# FULL_WAVE_RECTIFIER_PCB.net
KiCad netlist of a schematic drawn in EasyEDA
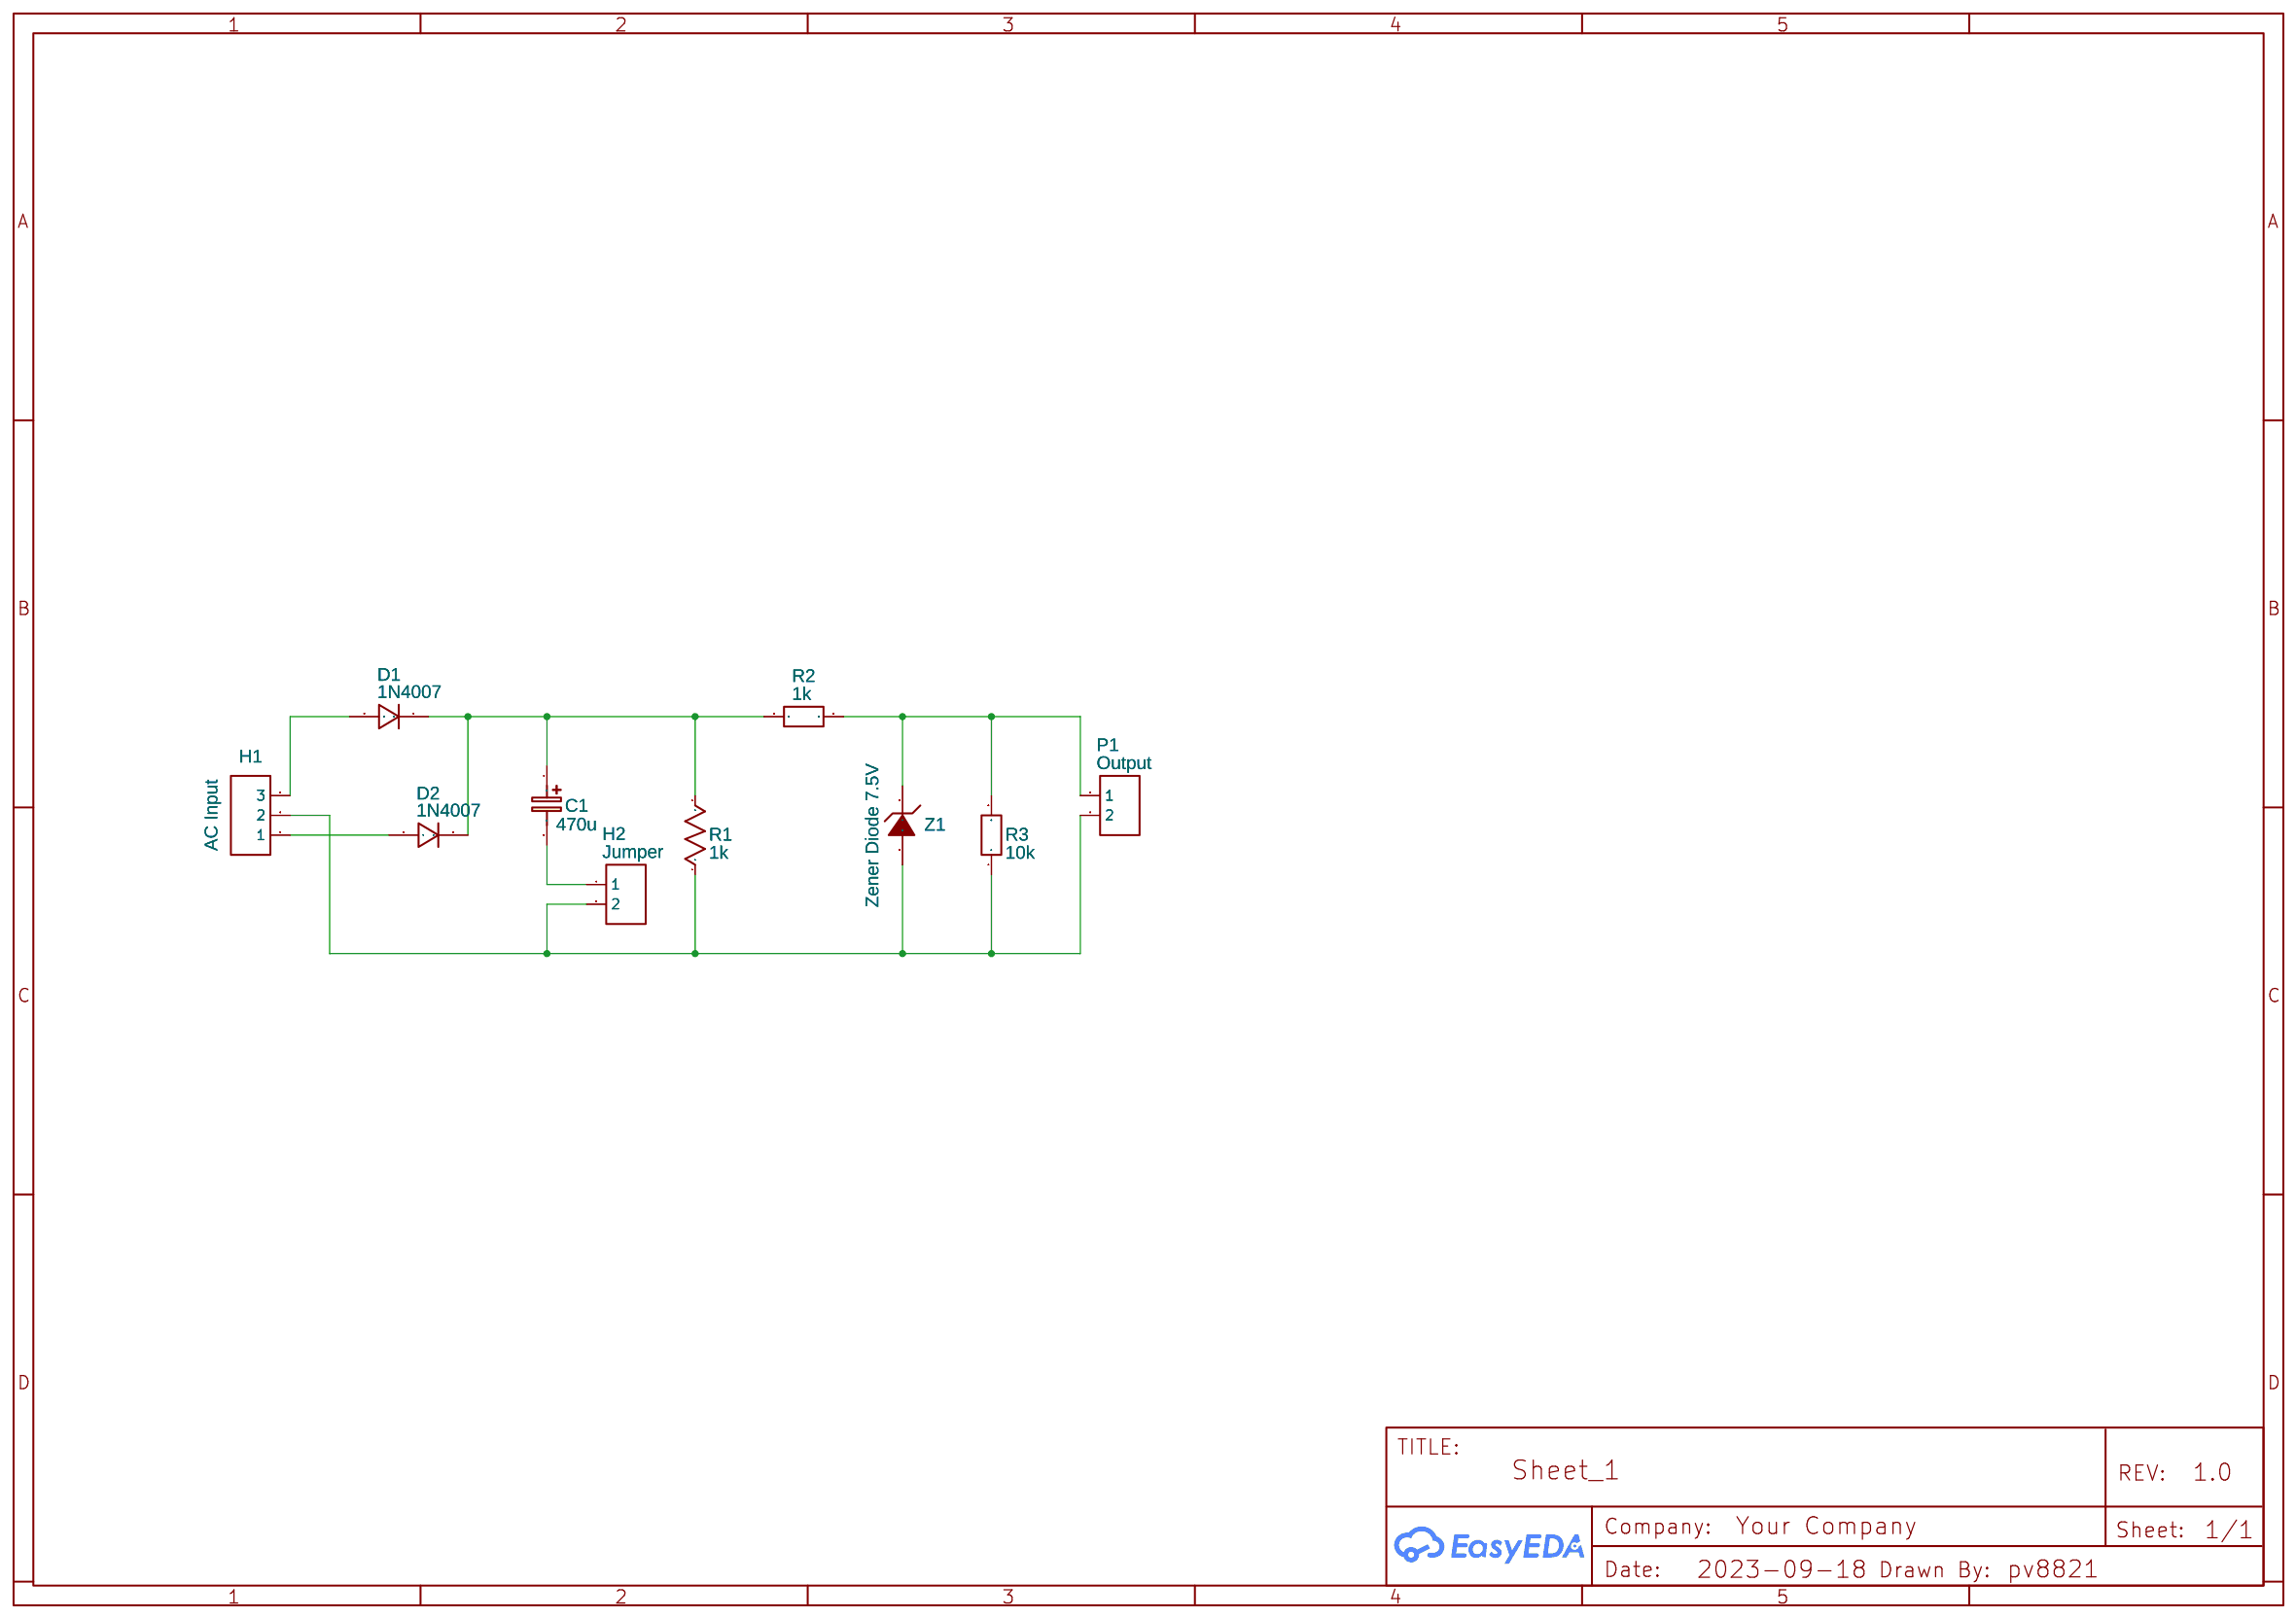
[diagram p0: schematic sheet]

(export (version "E")
  (design (tool "Eeschema 10.0.6"))
  (components
    (comp (ref "C1") (value "470u") (libsource (lib "") (part "CE_TH_D5.0×F2.0_EU")))
    (comp (ref "D1")
      (value "1N4007")
      (fields (field (name "Manufacturer") "SEMTECH"))
      (libsource (lib "") (part "1N4007"))
    )
    (comp (ref "D2")
      (value "1N4007")
      (fields (field (name "Manufacturer") "SEMTECH"))
      (libsource (lib "") (part "1N4007"))
    )
    (comp (ref "H1") (value "AC Input") (libsource (lib "") (part "HDR-F-2.54_1x3")))
    (comp (ref "H2") (value "Jumper") (libsource (lib "") (part "HDR-F-2.54_1x2")))
    (comp (ref "P1") (value "Output") (libsource (lib "") (part "CONN-TH_2P-P5.00")))
    (comp (ref "R1") (value "1k") (libsource (lib "") (part "R_AXIAL-0.5_US")))
    (comp (ref "R2") (value "1k") (libsource (lib "") (part "R_AXIAL-0.5_EU_1")))
    (comp (ref "R3") (value "10k") (libsource (lib "") (part "R_AXIAL-0.5_EU")))
    (comp (ref "Z1")
      (value "Zener Diode 7.5V")
      (fields (field (name "Manufacturer Part") "1N5349BRLG") (field (name "Manufacturer") "onsemi(安森美)"))
      (libsource (lib "") (part "1N5349BRLG"))
    )
  )
  (nets
    (net (code "1") (name "Net-(C1-Pad1)") (class "Default")
      (node (ref "C1") (pin "1") (pinfunction "1_1") (pintype "unspecified"))
      (node (ref "D1") (pin "1") (pinfunction "1_1") (pintype "unspecified"))
      (node (ref "D2") (pin "1") (pinfunction "1_1") (pintype "unspecified"))
      (node (ref "R1") (pin "2") (pinfunction "2_2") (pintype "unspecified"))
      (node (ref "R2") (pin "1") (pinfunction "1_1") (pintype "unspecified"))
    )
    (net (code "2") (name "Net-(C1-Pad2)") (class "Default")
      (node (ref "C1") (pin "2") (pinfunction "2_2") (pintype "unspecified"))
      (node (ref "H2") (pin "1") (pinfunction "1_1") (pintype "input"))
    )
    (net (code "3") (name "Net-(D1-Pad2)") (class "Default")
      (node (ref "D1") (pin "2") (pinfunction "2_2") (pintype "unspecified"))
      (node (ref "H1") (pin "3") (pinfunction "3_3") (pintype "input"))
    )
    (net (code "4") (name "Net-(D2-Pad2)") (class "Default")
      (node (ref "D2") (pin "2") (pinfunction "2_2") (pintype "unspecified"))
      (node (ref "H1") (pin "1") (pinfunction "1_1") (pintype "input"))
    )
    (net (code "5") (name "Net-(Z1-A)") (class "Default")
      (node (ref "P1") (pin "1") (pinfunction "1_1") (pintype "unspecified"))
      (node (ref "R2") (pin "2") (pinfunction "2_2") (pintype "unspecified"))
      (node (ref "R3") (pin "2") (pinfunction "2_2") (pintype "unspecified"))
      (node (ref "Z1") (pin "2") (pinfunction "A_2") (pintype "unspecified"))
    )
    (net (code "6") (name "Net-(Z1-C)") (class "Default")
      (node (ref "H1") (pin "2") (pinfunction "2_2") (pintype "input"))
      (node (ref "H2") (pin "2") (pinfunction "2_2") (pintype "input"))
      (node (ref "P1") (pin "2") (pinfunction "2_2") (pintype "unspecified"))
      (node (ref "R1") (pin "1") (pinfunction "1_1") (pintype "unspecified"))
      (node (ref "R3") (pin "1") (pinfunction "1_1") (pintype "unspecified"))
      (node (ref "Z1") (pin "1") (pinfunction "C_1") (pintype "unspecified"))
    )
  )
)
